# Urukul_DIOT_Connectors_P1_P6.net
KiCad netlist of a schematic drawn in Altium Designer
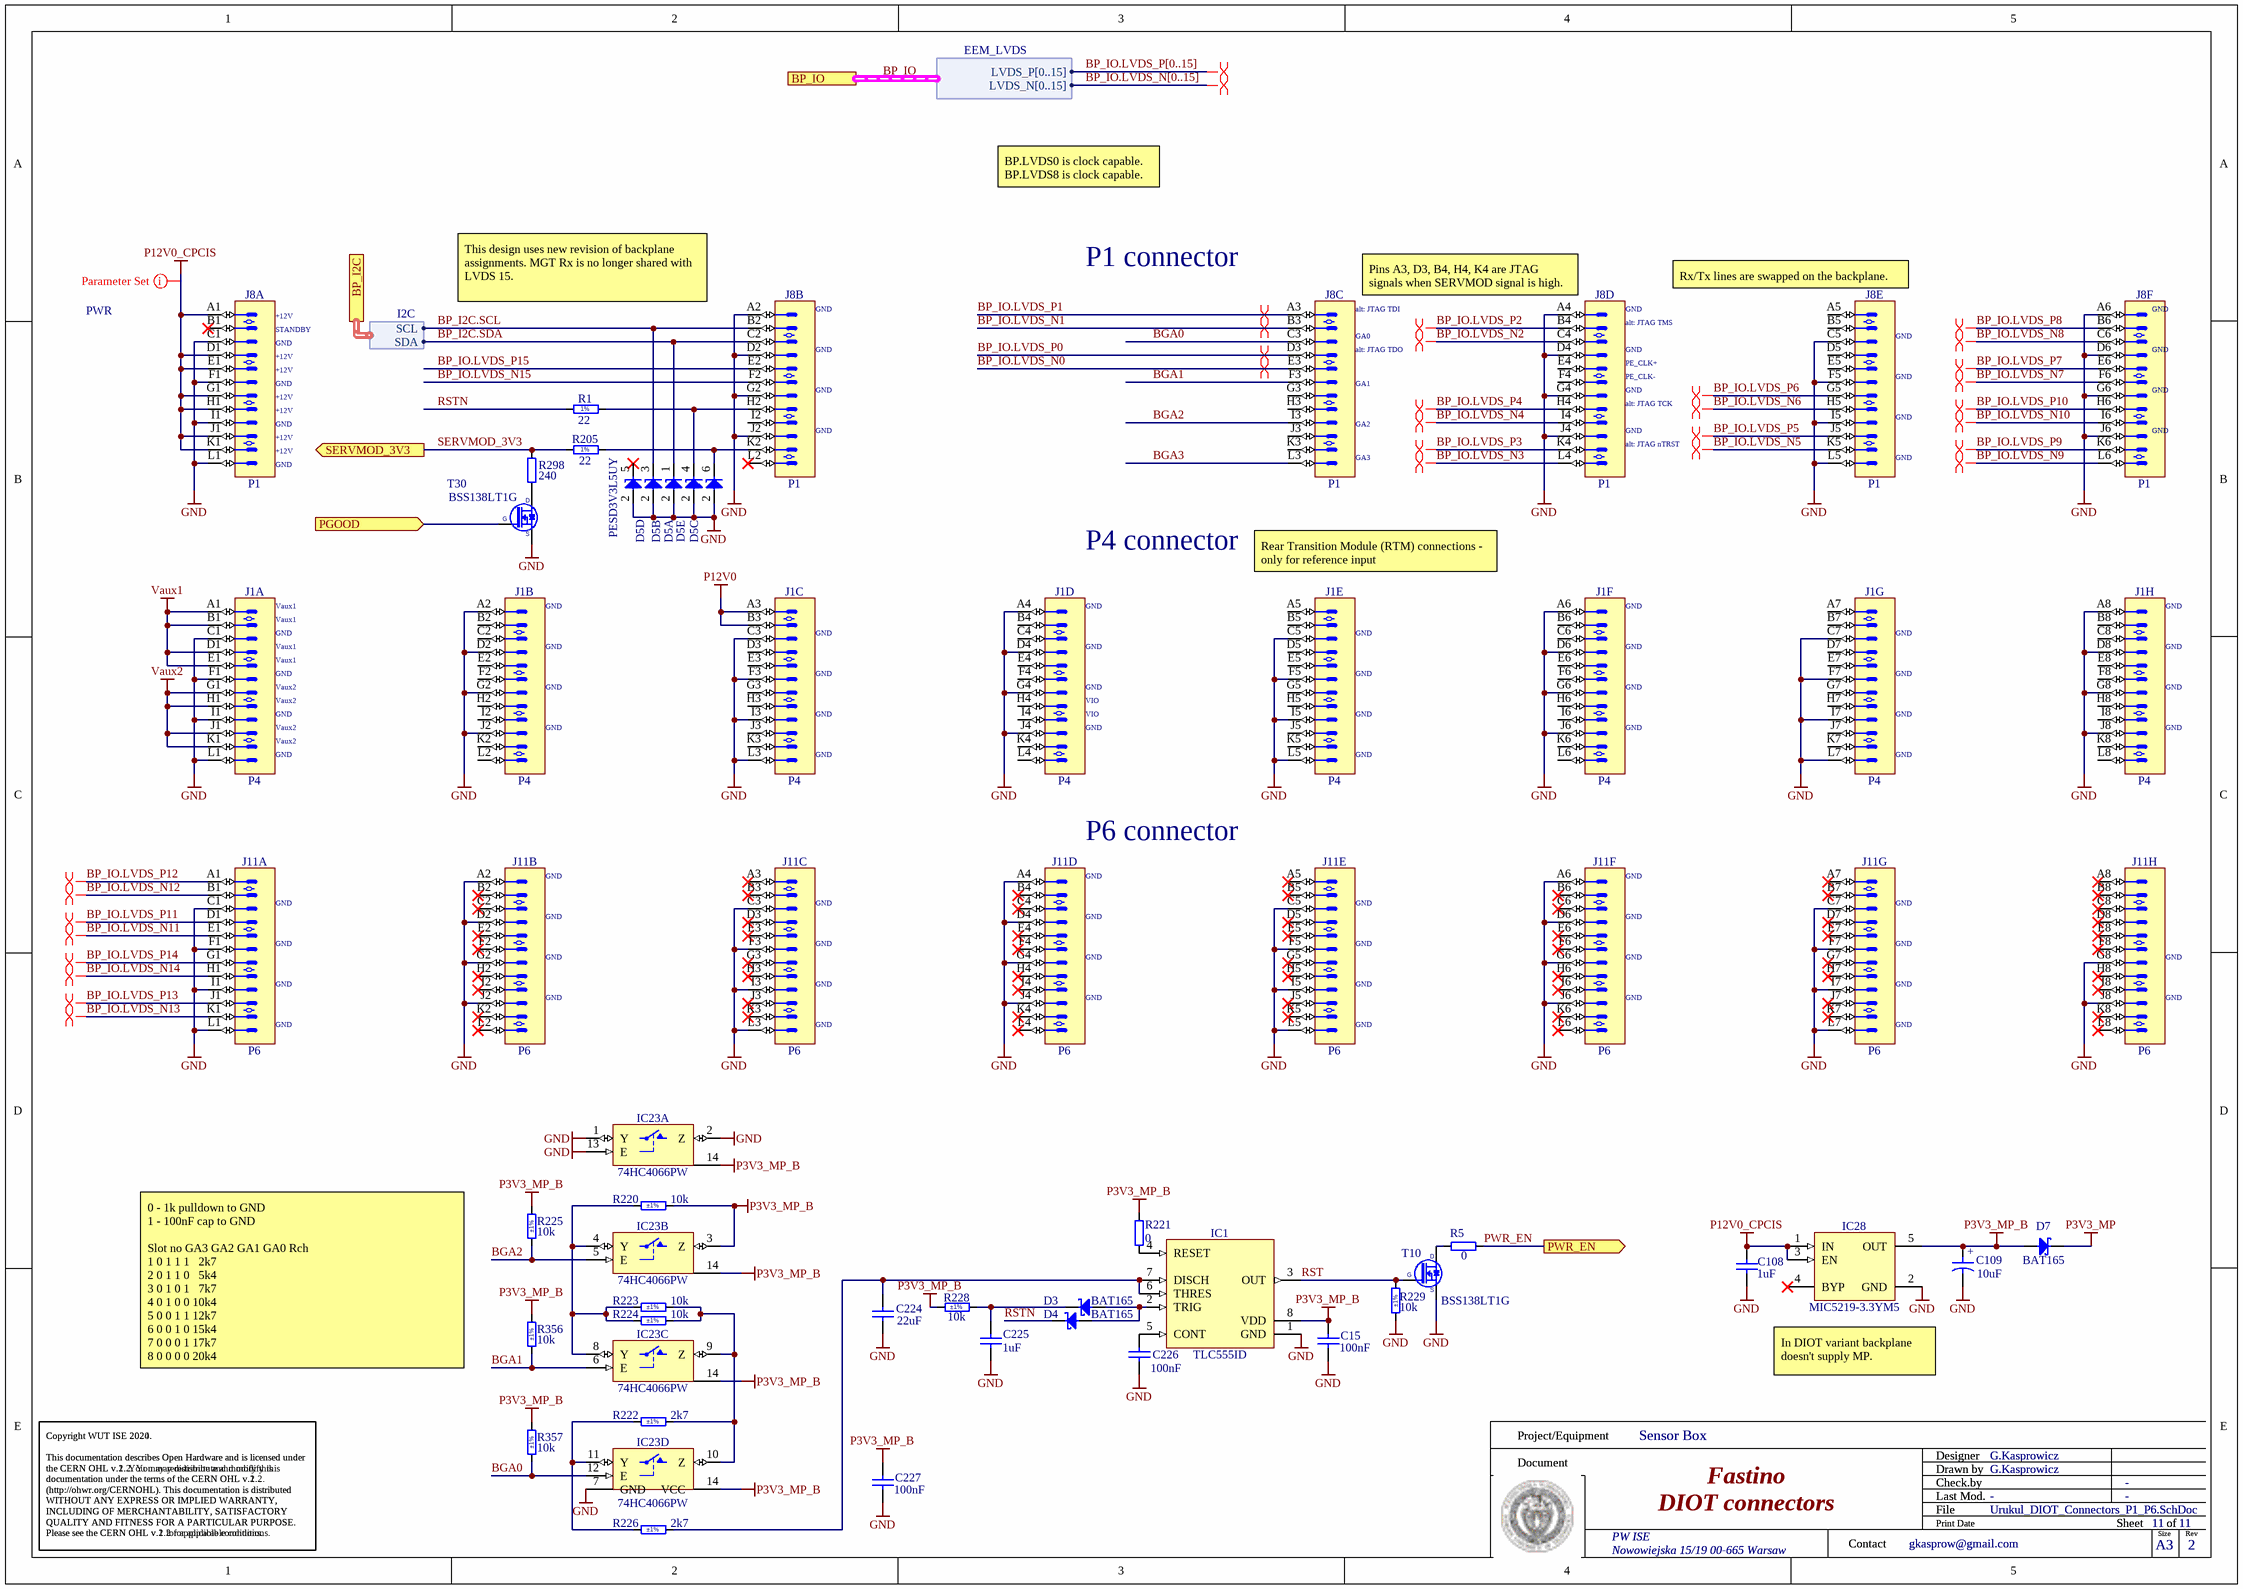
[diagram p0: Urukul_DIOT_Connectors_P1_P6.SchDoc]

(export (version "E")
  (design (tool "Eeschema 10.0.6"))
  (components
    (comp (ref "C15")
      (value "100nF")
      (footprint "CAPC1005X55N")
      (description "Non-polarised capacitor")
      (fields
        (field (name "PART NUMBER") "CC0402_100NF_16V_10%_X5R")
        (field (name "VOLTAGE") "16V")
        (field (name "AUTHOR") "CERN DEM JLC")
      )
      (libsource (lib "Capacitors") (part "Capacitor - non polarized"))
    )
    (comp (ref "C108")
      (value "1uF")
      (footprint "CAPC1608X87N")
      (description "Non-polarised capacitor")
      (fields
        (field (name "PART NUMBER") "CC0603_1UF_25V_10%_X7R")
        (field (name "VOLTAGE") "25V")
        (field (name "AUTHOR") "CERN DEM JLC")
      )
      (libsource (lib "Capacitors") (part "Capacitor - non polarized"))
    )
    (comp (ref "C109")
      (value "10uF")
      (footprint "CAPMP3216X180N")
      (description "Polarised capacitor")
      (fields
        (field (name "PART NUMBER") "CTE3216-18_10UF_16V_20%_AVX_TCJ")
        (field (name "VOLTAGE") "16V")
        (field (name "AUTHOR") "CERN DEM JLC")
      )
      (libsource (lib "Capacitors") (part "Capacitor - polarized"))
    )
    (comp (ref "C224")
      (value "22uF")
      (footprint "CAPC1608X90N")
      (description "Non-polarised capacitor")
      (fields
        (field (name "MANUFACTURER") "GENERIC")
        (field (name "PART NUMBER") "CC0603_22UF_6.3V_20%_X5R")
        (field (name "AUTHOR") "CERN DEM JLC")
      )
      (libsource (lib "Capacitors") (part "Capacitor - non polarized"))
    )
    (comp (ref "C225")
      (value "1uF")
      (footprint "CAPC1005X55N")
      (description "Non-polarised capacitor")
      (fields
        (field (name "PART NUMBER") "CC0402_1UF_16V_10%_X5R")
        (field (name "VOLTAGE") "16V")
        (field (name "AUTHOR") "CERN DEM JLC")
      )
      (libsource (lib "Capacitors") (part "Capacitor - non polarized"))
    )
    (comp (ref "C226")
      (value "100nF")
      (footprint "CAPC1005X55N")
      (description "Non-polarised capacitor")
      (fields
        (field (name "PART NUMBER") "CC0402_100NF_16V_10%_X5R")
        (field (name "VOLTAGE") "16V")
        (field (name "AUTHOR") "CERN DEM JLC")
      )
      (libsource (lib "Capacitors") (part "Capacitor - non polarized"))
    )
    (comp (ref "C227")
      (value "100nF")
      (footprint "CAPC1005X55N")
      (description "Non-polarised capacitor")
      (fields
        (field (name "PART NUMBER") "CC0402_100NF_16V_10%_X5R")
        (field (name "VOLTAGE") "16V")
        (field (name "AUTHOR") "CERN DEM JLC")
      )
      (libsource (lib "Capacitors") (part "Capacitor - non polarized"))
    )
    (comp (ref "D3")
      (value "BAT165")
      (footprint "SOD2512X110N")
      (description "Schottky Diode")
      (fields
        (field (name "MANUFACTURER") "INFINEON")
        (field (name "VOLTAGE") "40V")
        (field (name "AUTHOR") "CERN DEM JLC")
      )
      (libsource (lib "ICs And Semiconductors") (part "Diode Schottky"))
    )
    (comp (ref "D4")
      (value "BAT165")
      (footprint "SOD2512X110N")
      (description "Schottky Diode")
      (fields
        (field (name "MANUFACTURER") "INFINEON")
        (field (name "VOLTAGE") "40V")
        (field (name "AUTHOR") "CERN DEM JLC")
      )
      (libsource (lib "ICs And Semiconductors") (part "Diode Schottky"))
    )
    (comp (ref "D5")
      (value "PESD3V3L5UY")
      (footprint "SOT65P210X110-6N")
      (description "Fivefold ESD Protection Diode Arrays")
      (fields
        (field (name "VOLTAGE") "3.3V")
        (field (name "POWER") "200W")
        (field (name "AUTHOR") "CERN DEM WB")
      )
      (libsource (lib "ICs And Semiconductors") (part "PESD Array 5diodes 6pins Common anode2"))
    )
    (comp (ref "D7")
      (value "BAT165")
      (footprint "SOD2512X110N")
      (description "Schottky Diode")
      (fields
        (field (name "MANUFACTURER") "INFINEON")
        (field (name "VOLTAGE") "40V")
        (field (name "AUTHOR") "CERN DEM JLC")
      )
      (libsource (lib "ICs And Semiconductors") (part "Diode Schottky"))
    )
    (comp (ref "IC1")
      (value "TLC555ID")
      (footprint "SOIC127P600X175-8N")
      (description "LinCMOS Timer")
      (fields (field (name "MANUFACTURER") "TEXAS INSTRUMENTS") (field (name "AUTHOR") "CERN DEM JMW"))
      (libsource (lib "ICs And Semiconductors") (part "TLC555"))
    )
    (comp (ref "IC23")
      (value "74HC4066PW")
      (footprint "SOP65P640X110-14N")
      (fields (field (name "MANUFACTURER") "NXP SEMICONDUCTORS") (field (name "AUTHOR") "CERN DEM JLC"))
      (libsource (lib "ICs And Semiconductors") (part "4066"))
    )
    (comp (ref "IC28")
      (value "MIC5219-3.3YM5")
      (footprint "SOT95P280X145-5N")
      (description "500mA Peak Output LDO Regulator")
      (fields (field (name "MANUFACTURER") "MICROCHIP TECHNOLOGY") (field (name "AUTHOR") "CERN DEM WB"))
      (libsource (lib "ICs And Semiconductors") (part "MIC5219-X.XYM5"))
    )
    (comp (ref "J1")
      (value "P4")
      (footprint "AMPHENOL_10052837-101LF")
      (description "96 Contacts Header, 8 Columns, 4 Pairs per Column")
      (fields
        (field (name "PART NUMBER") "AMPHENOL_10052837-101LF")
        (field (name "MANUFACTURER") "AMPHENOL")
        (field (name "AUTHOR") "CERN DEM MR")
      )
      (libsource (lib "Connectors") (part "AMPHENOL_10052837-101LF"))
    )
    (comp (ref "J8")
      (value "P1")
      (footprint "AMPHENOL_10052825-101LF")
      (description "72 Contacts Header, 6 Columns, 4 Pairs per Column")
      (fields
        (field (name "PART NUMBER") "AMPHENOL_10052825-101LF")
        (field (name "MANUFACTURER") "AMPHENOL")
        (field (name "AUTHOR") "CERN DEM MR")
      )
      (libsource (lib "Connectors") (part "AMPHENOL_10052825-101LF"))
    )
    (comp (ref "J11")
      (value "P6")
      (footprint "AMPHENOL_10052838-101LF")
      (description "96 Contacts Header, 8 Columns, 4 Pairs per Column")
      (fields
        (field (name "PART NUMBER") "AMPHENOL_10052838-101LF")
        (field (name "MANUFACTURER") "AMPHENOL")
        (field (name "AUTHOR") "CERN DEM MR")
      )
      (libsource (lib "Connectors") (part "AMPHENOL_10052838-101LF"))
    )
    (comp (ref "R1")
      (value "22")
      (footprint "RESC1005X40N")
      (description "Resistor - 1%")
      (fields
        (field (name "PART NUMBER") "R0402_22R_1%_0.0625W_100PPM")
        (field (name "POWER") "0.0625W")
        (field (name "AUTHOR") "CERN DEM JLC")
      )
      (libsource (lib "Resistors") (part "Resistor - 1%"))
    )
    (comp (ref "R5")
      (value "0")
      (footprint "RESC1005X40N")
      (description "Resistor")
      (fields
        (field (name "PART NUMBER") "R0402_0R_JUMPER")
        (field (name "MANUFACTURER") "GENERIC")
        (field (name "AUTHOR") "CERN DEM JLC")
      )
      (libsource (lib "Resistors") (part "Resistor"))
    )
    (comp (ref "R205")
      (value "22")
      (footprint "RESC1005X40N")
      (description "Resistor - 1%")
      (fields
        (field (name "PART NUMBER") "R0402_22R_1%_0.0625W_100PPM")
        (field (name "POWER") "0.0625W")
        (field (name "AUTHOR") "CERN DEM JLC")
      )
      (libsource (lib "Resistors") (part "Resistor - 1%"))
    )
    (comp (ref "R220")
      (value "10k")
      (footprint "RESC1005X40N")
      (description "Resistor - 1%")
      (fields
        (field (name "PART NUMBER") "R0402_10K_1%_0.0625W_100PPM")
        (field (name "POWER") "0.0625W")
        (field (name "TOLERANCE") "±1%")
        (field (name "AUTHOR") "CERN DEM JLC")
      )
      (libsource (lib "Resistors") (part "Resistor - 1%"))
    )
    (comp (ref "R221")
      (value "0")
      (footprint "RESC1005X40N")
      (description "Resistor")
      (fields
        (field (name "PART NUMBER") "R0402_0R_JUMPER")
        (field (name "MANUFACTURER") "GENERIC")
        (field (name "AUTHOR") "CERN DEM JLC")
      )
      (libsource (lib "Resistors") (part "Resistor"))
    )
    (comp (ref "R222")
      (value "2k7")
      (footprint "RESC1608X55N")
      (description "Resistor - 1%")
      (fields
        (field (name "PART NUMBER") "R0603_2K7_1%_0.1W_100PPM")
        (field (name "POWER") "0.1W")
        (field (name "TOLERANCE") "±1%")
        (field (name "AUTHOR") "CERN DEM JLC")
      )
      (libsource (lib "Resistors") (part "Resistor - 1%"))
    )
    (comp (ref "R223")
      (value "10k")
      (footprint "RESC1005X40N")
      (description "Resistor - 1%")
      (fields
        (field (name "PART NUMBER") "R0402_10K_1%_0.0625W_100PPM")
        (field (name "POWER") "0.0625W")
        (field (name "TOLERANCE") "±1%")
        (field (name "AUTHOR") "CERN DEM JLC")
      )
      (libsource (lib "Resistors") (part "Resistor - 1%"))
    )
    (comp (ref "R224")
      (value "10k")
      (footprint "RESC1005X40N")
      (description "Resistor - 1%")
      (fields
        (field (name "PART NUMBER") "R0402_10K_1%_0.0625W_100PPM")
        (field (name "POWER") "0.0625W")
        (field (name "TOLERANCE") "±1%")
        (field (name "AUTHOR") "CERN DEM JLC")
      )
      (libsource (lib "Resistors") (part "Resistor - 1%"))
    )
    (comp (ref "R225")
      (value "10k")
      (footprint "RESC1005X40N")
      (description "Resistor - 1%")
      (fields
        (field (name "PART NUMBER") "R0402_10K_1%_0.0625W_100PPM")
        (field (name "POWER") "0.0625W")
        (field (name "TOLERANCE") "±1%")
        (field (name "AUTHOR") "CERN DEM JLC")
      )
      (libsource (lib "Resistors") (part "Resistor - 1%"))
    )
    (comp (ref "R226")
      (value "2k7")
      (footprint "RESC1608X55N")
      (description "Resistor - 1%")
      (fields
        (field (name "PART NUMBER") "R0603_2K7_1%_0.1W_100PPM")
        (field (name "POWER") "0.1W")
        (field (name "TOLERANCE") "±1%")
        (field (name "AUTHOR") "CERN DEM JLC")
      )
      (libsource (lib "Resistors") (part "Resistor - 1%"))
    )
    (comp (ref "R228")
      (value "10k")
      (footprint "RESC1005X40N")
      (description "Resistor - 1%")
      (fields
        (field (name "TOLERANCE") "±1%")
        (field (name "PART NUMBER") "R0402_10K_1%_0.0625W_100PPM")
        (field (name "POWER") "0.0625W")
        (field (name "AUTHOR") "CERN DEM JLC")
      )
      (libsource (lib "Resistors") (part "Resistor - 1%"))
    )
    (comp (ref "R229")
      (value "10k")
      (footprint "RESC1005X40N")
      (description "Resistor - 1%")
      (fields
        (field (name "TOLERANCE") "±1%")
        (field (name "PART NUMBER") "R0402_10K_1%_0.0625W_100PPM")
        (field (name "POWER") "0.0625W")
        (field (name "AUTHOR") "CERN DEM JLC")
      )
      (libsource (lib "Resistors") (part "Resistor - 1%"))
    )
    (comp (ref "R298")
      (value "240")
      (footprint "RESC1005X40N")
      (description "Resistor - 1%")
      (fields
        (field (name "PART NUMBER") "R0402_240R_1%_0.0625W_100PPM")
        (field (name "POWER") "0.0625W")
        (field (name "AUTHOR") "CERN DEM JLC")
      )
      (libsource (lib "Resistors") (part "Resistor - 1%"))
    )
    (comp (ref "R356")
      (value "10k")
      (footprint "RESC1005X40N")
      (description "Resistor - 1%")
      (fields
        (field (name "PART NUMBER") "R0402_10K_1%_0.0625W_100PPM")
        (field (name "POWER") "0.0625W")
        (field (name "TOLERANCE") "±1%")
        (field (name "AUTHOR") "CERN DEM JLC")
      )
      (libsource (lib "Resistors") (part "Resistor - 1%"))
    )
    (comp (ref "R357")
      (value "10k")
      (footprint "RESC1005X40N")
      (description "Resistor - 1%")
      (fields
        (field (name "PART NUMBER") "R0402_10K_1%_0.0625W_100PPM")
        (field (name "POWER") "0.0625W")
        (field (name "TOLERANCE") "±1%")
        (field (name "AUTHOR") "CERN DEM JLC")
      )
      (libsource (lib "Resistors") (part "Resistor - 1%"))
    )
    (comp (ref "T10")
      (value "BSS138LT1G")
      (footprint "SOT95P240X110-3N")
      (description "N-CHANNEL MOSFET WITH DIODE")
      (fields (field (name "MANUFACTURER") "ON SEMICONDUCTOR") (field (name "AUTHOR") "CERN DEM JLC"))
      (libsource (lib "ICs And Semiconductors") (part "N-MOSFET-D 1G 2S 3D"))
    )
    (comp (ref "T30")
      (value "BSS138LT1G")
      (footprint "SOT95P240X110-3N")
      (description "N-CHANNEL MOSFET WITH DIODE")
      (fields (field (name "MANUFACTURER") "ON SEMICONDUCTOR") (field (name "AUTHOR") "CERN DEM JLC"))
      (libsource (lib "ICs And Semiconductors") (part "N-MOSFET-D 1G 2S 3D"))
    )
  )
  (nets
    (net (code "3") (name "/BGA0") (class "Default")
      (node (ref "IC23") (pin "12") (pinfunction "E_12") (pintype "input"))
      (node (ref "J8") (pin "C3") (pinfunction "C3_C3") (pintype "bidirectional"))
      (node (ref "R357") (pin "1") (pinfunction "1_1") (pintype "passive"))
    )
    (net (code "4") (name "/BGA1") (class "Default")
      (node (ref "IC23") (pin "6") (pinfunction "E_6") (pintype "input"))
      (node (ref "J8") (pin "F3") (pinfunction "F3_F3") (pintype "bidirectional"))
      (node (ref "R356") (pin "1") (pinfunction "1_1") (pintype "passive"))
    )
    (net (code "5") (name "/BGA2") (class "Default")
      (node (ref "IC23") (pin "5") (pinfunction "E_5") (pintype "input"))
      (node (ref "J8") (pin "I3") (pinfunction "I3_I3") (pintype "bidirectional"))
      (node (ref "R225") (pin "1") (pinfunction "1_1") (pintype "passive"))
    )
    (net (code "6") (name "/BGA3") (class "Default")
      (node (ref "J8") (pin "L3") (pinfunction "L3_L3") (pintype "bidirectional"))
    )
    (net (code "7") (name "/BP_I2C.SCL") (class "Default")
      (node (ref "D5") (pin "3") (pinfunction "C_3") (pintype "passive"))
      (node (ref "J8") (pin "B2") (pinfunction "B2_B2") (pintype "bidirectional"))
    )
    (net (code "8") (name "/BP_I2C.SDA") (class "Default")
      (node (ref "D5") (pin "1") (pinfunction "C_1") (pintype "passive"))
      (node (ref "J8") (pin "C2") (pinfunction "C2_C2") (pintype "bidirectional"))
    )
    (net (code "9") (name "/BP_IO.LVDS_N0") (class "Default")
      (node (ref "J8") (pin "E3") (pinfunction "E3_E3") (pintype "bidirectional"))
    )
    (net (code "10") (name "/BP_IO.LVDS_N1") (class "Default")
      (node (ref "J8") (pin "B3") (pinfunction "B3_B3") (pintype "bidirectional"))
    )
    (net (code "11") (name "/BP_IO.LVDS_N2") (class "Default")
      (node (ref "J8") (pin "C4") (pinfunction "C4_C4") (pintype "bidirectional"))
    )
    (net (code "12") (name "/BP_IO.LVDS_N3") (class "Default")
      (node (ref "J8") (pin "L4") (pinfunction "L4_L4") (pintype "bidirectional"))
    )
    (net (code "13") (name "/BP_IO.LVDS_N4") (class "Default")
      (node (ref "J8") (pin "I4") (pinfunction "I4_I4") (pintype "bidirectional"))
    )
    (net (code "14") (name "/BP_IO.LVDS_N5") (class "Default")
      (node (ref "J8") (pin "K5") (pinfunction "K5_K5") (pintype "bidirectional"))
    )
    (net (code "15") (name "/BP_IO.LVDS_N6") (class "Default")
      (node (ref "J8") (pin "H5") (pinfunction "H5_H5") (pintype "bidirectional"))
    )
    (net (code "16") (name "/BP_IO.LVDS_N7") (class "Default")
      (node (ref "J8") (pin "F6") (pinfunction "F6_F6") (pintype "bidirectional"))
    )
    (net (code "17") (name "/BP_IO.LVDS_N8") (class "Default")
      (node (ref "J8") (pin "C6") (pinfunction "C6_C6") (pintype "bidirectional"))
    )
    (net (code "18") (name "/BP_IO.LVDS_N9") (class "Default")
      (node (ref "J8") (pin "L6") (pinfunction "L6_L6") (pintype "bidirectional"))
    )
    (net (code "19") (name "/BP_IO.LVDS_N10") (class "Default")
      (node (ref "J8") (pin "I6") (pinfunction "I6_I6") (pintype "bidirectional"))
    )
    (net (code "20") (name "/BP_IO.LVDS_N11") (class "Default")
      (node (ref "J11") (pin "E1") (pinfunction "E1_E1") (pintype "bidirectional"))
    )
    (net (code "21") (name "/BP_IO.LVDS_N12") (class "Default")
      (node (ref "J11") (pin "B1") (pinfunction "B1_B1") (pintype "bidirectional"))
    )
    (net (code "22") (name "/BP_IO.LVDS_N13") (class "Default")
      (node (ref "J11") (pin "K1") (pinfunction "K1_K1") (pintype "bidirectional"))
    )
    (net (code "23") (name "/BP_IO.LVDS_N14") (class "Default")
      (node (ref "J11") (pin "H1") (pinfunction "H1_H1") (pintype "bidirectional"))
    )
    (net (code "24") (name "/BP_IO.LVDS_N15") (class "Default")
      (node (ref "J8") (pin "F2") (pinfunction "F2_F2") (pintype "bidirectional"))
    )
    (net (code "26") (name "/BP_IO.LVDS_P0") (class "Default")
      (node (ref "J8") (pin "D3") (pinfunction "D3_D3") (pintype "bidirectional"))
    )
    (net (code "27") (name "/BP_IO.LVDS_P1") (class "Default")
      (node (ref "J8") (pin "A3") (pinfunction "A3_A3") (pintype "bidirectional"))
    )
    (net (code "28") (name "/BP_IO.LVDS_P2") (class "Default")
      (node (ref "J8") (pin "B4") (pinfunction "B4_B4") (pintype "bidirectional"))
    )
    (net (code "29") (name "/BP_IO.LVDS_P3") (class "Default")
      (node (ref "J8") (pin "K4") (pinfunction "K4_K4") (pintype "bidirectional"))
    )
    (net (code "30") (name "/BP_IO.LVDS_P4") (class "Default")
      (node (ref "J8") (pin "H4") (pinfunction "H4_H4") (pintype "bidirectional"))
    )
    (net (code "31") (name "/BP_IO.LVDS_P5") (class "Default")
      (node (ref "J8") (pin "J5") (pinfunction "J5_J5") (pintype "bidirectional"))
    )
    (net (code "32") (name "/BP_IO.LVDS_P6") (class "Default")
      (node (ref "J8") (pin "G5") (pinfunction "G5_G5") (pintype "bidirectional"))
    )
    (net (code "33") (name "/BP_IO.LVDS_P7") (class "Default")
      (node (ref "J8") (pin "E6") (pinfunction "E6_E6") (pintype "bidirectional"))
    )
    (net (code "34") (name "/BP_IO.LVDS_P8") (class "Default")
      (node (ref "J8") (pin "B6") (pinfunction "B6_B6") (pintype "bidirectional"))
    )
    (net (code "35") (name "/BP_IO.LVDS_P9") (class "Default")
      (node (ref "J8") (pin "K6") (pinfunction "K6_K6") (pintype "bidirectional"))
    )
    (net (code "36") (name "/BP_IO.LVDS_P10") (class "Default")
      (node (ref "J8") (pin "H6") (pinfunction "H6_H6") (pintype "bidirectional"))
    )
    (net (code "37") (name "/BP_IO.LVDS_P11") (class "Default")
      (node (ref "J11") (pin "D1") (pinfunction "D1_D1") (pintype "bidirectional"))
    )
    (net (code "38") (name "/BP_IO.LVDS_P12") (class "Default")
      (node (ref "J11") (pin "A1") (pinfunction "A1_A1") (pintype "bidirectional"))
    )
    (net (code "39") (name "/BP_IO.LVDS_P13") (class "Default")
      (node (ref "J11") (pin "J1") (pinfunction "J1_J1") (pintype "bidirectional"))
    )
    (net (code "40") (name "/BP_IO.LVDS_P14") (class "Default")
      (node (ref "J11") (pin "G1") (pinfunction "G1_G1") (pintype "bidirectional"))
    )
    (net (code "41") (name "/BP_IO.LVDS_P15") (class "Default")
      (node (ref "J8") (pin "E2") (pinfunction "E2_E2") (pintype "bidirectional"))
    )
    (net (code "42") (name "/PGOOD") (class "Default")
      (node (ref "T30") (pin "1") (pinfunction "G_1") (pintype "passive"))
    )
    (net (code "43") (name "/PWR_EN") (class "Default")
      (node (ref "R5") (pin "1") (pinfunction "1_1") (pintype "passive"))
    )
    (net (code "44") (name "/RST") (class "Default")
      (node (ref "IC1") (pin "3") (pinfunction "OUT_3") (pintype "output"))
      (node (ref "R229") (pin "2") (pinfunction "2_2") (pintype "passive"))
      (node (ref "T10") (pin "1") (pinfunction "G_1") (pintype "passive"))
    )
    (net (code "45") (name "/RSTN") (class "Default")
      (node (ref "D4") (pin "1") (pinfunction "C_1") (pintype "passive"))
      (node (ref "R1") (pin "1") (pinfunction "1_1") (pintype "passive"))
    )
    (net (code "46") (name "/SERVMOD_3V3") (class "Default")
      (node (ref "R205") (pin "1") (pinfunction "1_1") (pintype "passive"))
      (node (ref "R298") (pin "2") (pinfunction "2_2") (pintype "passive"))
    )
    (net (code "50") (name "GND") (class "Default")
      (node (ref "C108") (pin "1") (pinfunction "1_1") (pintype "passive"))
      (node (ref "C109") (pin "2") (pinfunction "2_2") (pintype "passive"))
      (node (ref "C15") (pin "1") (pinfunction "1_1") (pintype "passive"))
      (node (ref "C224") (pin "1") (pinfunction "1_1") (pintype "passive"))
      (node (ref "C225") (pin "1") (pinfunction "1_1") (pintype "passive"))
      (node (ref "C226") (pin "1") (pinfunction "1_1") (pintype "passive"))
      (node (ref "C227") (pin "1") (pinfunction "1_1") (pintype "passive"))
      (node (ref "D5") (pin "2") (pinfunction "A_2") (pintype "passive"))
      (node (ref "IC1") (pin "1") (pinfunction "GND_1") (pintype "power_in"))
      (node (ref "IC23") (pin "1") (pinfunction "Y_1") (pintype "bidirectional"))
      (node (ref "IC23") (pin "13") (pinfunction "E_13") (pintype "input"))
      (node (ref "IC23") (pin "2") (pinfunction "Z_2") (pintype "bidirectional"))
      (node (ref "IC23") (pin "7") (pinfunction "GND_7") (pintype "power_in"))
      (node (ref "IC28") (pin "2") (pinfunction "GND_2") (pintype "power_in"))
      (node (ref "J1") (pin "A2") (pinfunction "A2_A2") (pintype "bidirectional"))
      (node (ref "J1") (pin "A4") (pinfunction "A4_A4") (pintype "bidirectional"))
      (node (ref "J1") (pin "A6") (pinfunction "A6_A6") (pintype "bidirectional"))
      (node (ref "J1") (pin "A8") (pinfunction "A8_A8") (pintype "bidirectional"))
      (node (ref "J1") (pin "C1") (pinfunction "C1_C1") (pintype "bidirectional"))
      (node (ref "J1") (pin "C3") (pinfunction "C3_C3") (pintype "bidirectional"))
      (node (ref "J1") (pin "C5") (pinfunction "C5_C5") (pintype "bidirectional"))
      (node (ref "J1") (pin "C7") (pinfunction "C7_C7") (pintype "bidirectional"))
      (node (ref "J1") (pin "D2") (pinfunction "D2_D2") (pintype "bidirectional"))
      (node (ref "J1") (pin "D4") (pinfunction "D4_D4") (pintype "bidirectional"))
      (node (ref "J1") (pin "D6") (pinfunction "D6_D6") (pintype "bidirectional"))
      (node (ref "J1") (pin "D8") (pinfunction "D8_D8") (pintype "bidirectional"))
      (node (ref "J1") (pin "F1") (pinfunction "F1_F1") (pintype "bidirectional"))
      (node (ref "J1") (pin "F3") (pinfunction "F3_F3") (pintype "bidirectional"))
      (node (ref "J1") (pin "F5") (pinfunction "F5_F5") (pintype "bidirectional"))
      (node (ref "J1") (pin "F7") (pinfunction "F7_F7") (pintype "bidirectional"))
      (node (ref "J1") (pin "G2") (pinfunction "G2_G2") (pintype "bidirectional"))
      (node (ref "J1") (pin "G4") (pinfunction "G4_G4") (pintype "bidirectional"))
      (node (ref "J1") (pin "G6") (pinfunction "G6_G6") (pintype "bidirectional"))
      (node (ref "J1") (pin "G8") (pinfunction "G8_G8") (pintype "bidirectional"))
      (node (ref "J1") (pin "I1") (pinfunction "I1_I1") (pintype "bidirectional"))
      (node (ref "J1") (pin "I3") (pinfunction "I3_I3") (pintype "bidirectional"))
      (node (ref "J1") (pin "I5") (pinfunction "I5_I5") (pintype "bidirectional"))
      (node (ref "J1") (pin "I7") (pinfunction "I7_I7") (pintype "bidirectional"))
      (node (ref "J1") (pin "J2") (pinfunction "J2_J2") (pintype "bidirectional"))
      (node (ref "J1") (pin "J4") (pinfunction "J4_J4") (pintype "bidirectional"))
      (node (ref "J1") (pin "J6") (pinfunction "J6_J6") (pintype "bidirectional"))
      (node (ref "J1") (pin "J8") (pinfunction "J8_J8") (pintype "bidirectional"))
      (node (ref "J1") (pin "L1") (pinfunction "L1_L1") (pintype "bidirectional"))
      (node (ref "J1") (pin "L3") (pinfunction "L3_L3") (pintype "bidirectional"))
      (node (ref "J1") (pin "L5") (pinfunction "L5_L5") (pintype "bidirectional"))
      (node (ref "J1") (pin "L7") (pinfunction "L7_L7") (pintype "bidirectional"))
      (node (ref "J11") (pin "A2") (pinfunction "A2_A2") (pintype "bidirectional"))
      (node (ref "J11") (pin "A4") (pinfunction "A4_A4") (pintype "bidirectional"))
      (node (ref "J11") (pin "A6") (pinfunction "A6_A6") (pintype "bidirectional"))
      (node (ref "J11") (pin "C1") (pinfunction "C1_C1") (pintype "bidirectional"))
      (node (ref "J11") (pin "C3") (pinfunction "C3_C3") (pintype "bidirectional"))
      (node (ref "J11") (pin "C5") (pinfunction "C5_C5") (pintype "bidirectional"))
      (node (ref "J11") (pin "C7") (pinfunction "C7_C7") (pintype "bidirectional"))
      (node (ref "J11") (pin "D2") (pinfunction "D2_D2") (pintype "bidirectional"))
      (node (ref "J11") (pin "D4") (pinfunction "D4_D4") (pintype "bidirectional"))
      (node (ref "J11") (pin "D6") (pinfunction "D6_D6") (pintype "bidirectional"))
      (node (ref "J11") (pin "F1") (pinfunction "F1_F1") (pintype "bidirectional"))
      (node (ref "J11") (pin "F3") (pinfunction "F3_F3") (pintype "bidirectional"))
      (node (ref "J11") (pin "F5") (pinfunction "F5_F5") (pintype "bidirectional"))
      (node (ref "J11") (pin "F7") (pinfunction "F7_F7") (pintype "bidirectional"))
      (node (ref "J11") (pin "G2") (pinfunction "G2_G2") (pintype "bidirectional"))
      (node (ref "J11") (pin "G4") (pinfunction "G4_G4") (pintype "bidirectional"))
      (node (ref "J11") (pin "G6") (pinfunction "G6_G6") (pintype "bidirectional"))
      (node (ref "J11") (pin "G8") (pinfunction "G8_G8") (pintype "bidirectional"))
      (node (ref "J11") (pin "I1") (pinfunction "I1_I1") (pintype "bidirectional"))
      (node (ref "J11") (pin "I3") (pinfunction "I3_I3") (pintype "bidirectional"))
      (node (ref "J11") (pin "I5") (pinfunction "I5_I5") (pintype "bidirectional"))
      (node (ref "J11") (pin "I7") (pinfunction "I7_I7") (pintype "bidirectional"))
      (node (ref "J11") (pin "J2") (pinfunction "J2_J2") (pintype "bidirectional"))
      (node (ref "J11") (pin "J4") (pinfunction "J4_J4") (pintype "bidirectional"))
      (node (ref "J11") (pin "J6") (pinfunction "J6_J6") (pintype "bidirectional"))
      (node (ref "J11") (pin "J8") (pinfunction "J8_J8") (pintype "bidirectional"))
      (node (ref "J11") (pin "L1") (pinfunction "L1_L1") (pintype "bidirectional"))
      (node (ref "J11") (pin "L3") (pinfunction "L3_L3") (pintype "bidirectional"))
      (node (ref "J11") (pin "L5") (pinfunction "L5_L5") (pintype "bidirectional"))
      (node (ref "J11") (pin "L7") (pinfunction "L7_L7") (pintype "bidirectional"))
      (node (ref "J8") (pin "A2") (pinfunction "A2_A2") (pintype "bidirectional"))
      (node (ref "J8") (pin "A4") (pinfunction "A4_A4") (pintype "bidirectional"))
      (node (ref "J8") (pin "A6") (pinfunction "A6_A6") (pintype "bidirectional"))
      (node (ref "J8") (pin "C1") (pinfunction "C1_C1") (pintype "bidirectional"))
      (node (ref "J8") (pin "C5") (pinfunction "C5_C5") (pintype "bidirectional"))
      (node (ref "J8") (pin "D2") (pinfunction "D2_D2") (pintype "bidirectional"))
      (node (ref "J8") (pin "D4") (pinfunction "D4_D4") (pintype "bidirectional"))
      (node (ref "J8") (pin "D6") (pinfunction "D6_D6") (pintype "bidirectional"))
      (node (ref "J8") (pin "F1") (pinfunction "F1_F1") (pintype "bidirectional"))
      (node (ref "J8") (pin "F5") (pinfunction "F5_F5") (pintype "bidirectional"))
      (node (ref "J8") (pin "G2") (pinfunction "G2_G2") (pintype "bidirectional"))
      (node (ref "J8") (pin "G4") (pinfunction "G4_G4") (pintype "bidirectional"))
      (node (ref "J8") (pin "G6") (pinfunction "G6_G6") (pintype "bidirectional"))
      (node (ref "J8") (pin "I1") (pinfunction "I1_I1") (pintype "bidirectional"))
      (node (ref "J8") (pin "I5") (pinfunction "I5_I5") (pintype "bidirectional"))
      (node (ref "J8") (pin "J2") (pinfunction "J2_J2") (pintype "bidirectional"))
      (node (ref "J8") (pin "J4") (pinfunction "J4_J4") (pintype "bidirectional"))
      (node (ref "J8") (pin "J6") (pinfunction "J6_J6") (pintype "bidirectional"))
      (node (ref "J8") (pin "L1") (pinfunction "L1_L1") (pintype "bidirectional"))
      (node (ref "J8") (pin "L5") (pinfunction "L5_L5") (pintype "bidirectional"))
      (node (ref "R229") (pin "1") (pinfunction "1_1") (pintype "passive"))
      (node (ref "T10") (pin "2") (pinfunction "S_2") (pintype "passive"))
      (node (ref "T30") (pin "2") (pinfunction "S_2") (pintype "passive"))
    )
    (net (code "51") (name "Net-(D3-A)") (class "Default")
      (node (ref "D3") (pin "2") (pinfunction "A_2") (pintype "passive"))
      (node (ref "D4") (pin "2") (pinfunction "A_2") (pintype "passive"))
      (node (ref "IC1") (pin "2") (pinfunction "TRIG_2") (pintype "input"))
    )
    (net (code "52") (name "Net-(D3-C)") (class "Default")
      (node (ref "C225") (pin "2") (pinfunction "2_2") (pintype "passive"))
      (node (ref "D3") (pin "1") (pinfunction "C_1") (pintype "passive"))
      (node (ref "R228") (pin "2") (pinfunction "2_2") (pintype "passive"))
    )
    (net (code "53") (name "Net-(D5C-C)") (class "Default")
      (node (ref "D5") (pin "4") (pinfunction "C_4") (pintype "passive"))
      (node (ref "J8") (pin "H2") (pinfunction "H2_H2") (pintype "bidirectional"))
      (node (ref "R1") (pin "2") (pinfunction "2_2") (pintype "passive"))
    )
    (net (code "54") (name "Net-(D5E-C)") (class "Default")
      (node (ref "D5") (pin "6") (pinfunction "C_6") (pintype "passive"))
      (node (ref "J8") (pin "K2") (pinfunction "K2_K2") (pintype "bidirectional"))
      (node (ref "R205") (pin "2") (pinfunction "2_2") (pintype "passive"))
    )
    (net (code "55") (name "Net-(IC1-CONT)") (class "Default")
      (node (ref "C226") (pin "2") (pinfunction "2_2") (pintype "passive"))
      (node (ref "IC1") (pin "5") (pinfunction "CONT_5") (pintype "input"))
    )
    (net (code "56") (name "Net-(IC1-DISCH)") (class "Default")
      (node (ref "C224") (pin "2") (pinfunction "2_2") (pintype "passive"))
      (node (ref "IC1") (pin "6") (pinfunction "THRES_6") (pintype "input"))
      (node (ref "IC1") (pin "7") (pinfunction "DISCH_7") (pintype "input"))
      (node (ref "R226") (pin "2") (pinfunction "2_2") (pintype "passive"))
    )
    (net (code "57") (name "Net-(IC1-RESET)") (class "Default")
      (node (ref "IC1") (pin "4") (pinfunction "RESET_4") (pintype "input"))
      (node (ref "R221") (pin "1") (pinfunction "1_1") (pintype "passive"))
    )
    (net (code "58") (name "Net-(IC23B-Y)") (class "Default")
      (node (ref "IC23") (pin "4") (pinfunction "Y_4") (pintype "bidirectional"))
      (node (ref "IC23") (pin "8") (pinfunction "Y_8") (pintype "bidirectional"))
      (node (ref "R220") (pin "1") (pinfunction "1_1") (pintype "passive"))
      (node (ref "R223") (pin "1") (pinfunction "1_1") (pintype "passive"))
      (node (ref "R224") (pin "1") (pinfunction "1_1") (pintype "passive"))
    )
    (net (code "59") (name "Net-(IC23C-Z)") (class "Default")
      (node (ref "IC23") (pin "10") (pinfunction "Z_10") (pintype "bidirectional"))
      (node (ref "IC23") (pin "9") (pinfunction "Z_9") (pintype "bidirectional"))
      (node (ref "R222") (pin "2") (pinfunction "2_2") (pintype "passive"))
      (node (ref "R223") (pin "2") (pinfunction "2_2") (pintype "passive"))
      (node (ref "R224") (pin "2") (pinfunction "2_2") (pintype "passive"))
    )
    (net (code "60") (name "Net-(IC23D-Y)") (class "Default")
      (node (ref "IC23") (pin "11") (pinfunction "Y_11") (pintype "bidirectional"))
      (node (ref "R222") (pin "1") (pinfunction "1_1") (pintype "passive"))
      (node (ref "R226") (pin "1") (pinfunction "1_1") (pintype "passive"))
    )
    (net (code "61") (name "Net-(T10-D)") (class "Default")
      (node (ref "R5") (pin "2") (pinfunction "2_2") (pintype "passive"))
      (node (ref "T10") (pin "3") (pinfunction "D_3") (pintype "passive"))
    )
    (net (code "62") (name "Net-(T30-D)") (class "Default")
      (node (ref "R298") (pin "1") (pinfunction "1_1") (pintype "passive"))
      (node (ref "T30") (pin "3") (pinfunction "D_3") (pintype "passive"))
    )
    (net (code "63") (name "P3V3_MP") (class "Default")
      (node (ref "D7") (pin "1") (pinfunction "C_1") (pintype "passive"))
    )
    (net (code "64") (name "P3V3_MP_B") (class "Default")
      (node (ref "C109") (pin "1") (pinfunction "1_1") (pintype "passive"))
      (node (ref "C15") (pin "2") (pinfunction "2_2") (pintype "passive"))
      (node (ref "C227") (pin "2") (pinfunction "2_2") (pintype "passive"))
      (node (ref "D7") (pin "2") (pinfunction "A_2") (pintype "passive"))
      (node (ref "IC1") (pin "8") (pinfunction "VDD_8") (pintype "power_in"))
      (node (ref "IC23") (pin "14") (pinfunction "VCC_14") (pintype "power_in"))
      (node (ref "IC23") (pin "3") (pinfunction "Z_3") (pintype "bidirectional"))
      (node (ref "IC28") (pin "5") (pinfunction "OUT_5") (pintype "power_in"))
      (node (ref "R220") (pin "2") (pinfunction "2_2") (pintype "passive"))
      (node (ref "R221") (pin "2") (pinfunction "2_2") (pintype "passive"))
      (node (ref "R225") (pin "2") (pinfunction "2_2") (pintype "passive"))
      (node (ref "R228") (pin "1") (pinfunction "1_1") (pintype "passive"))
      (node (ref "R356") (pin "2") (pinfunction "2_2") (pintype "passive"))
      (node (ref "R357") (pin "2") (pinfunction "2_2") (pintype "passive"))
    )
    (net (code "65") (name "P12V0") (class "Default")
      (node (ref "J1") (pin "A3") (pinfunction "A3_A3") (pintype "bidirectional"))
      (node (ref "J1") (pin "B3") (pinfunction "B3_B3") (pintype "bidirectional"))
    )
    (net (code "66") (name "P12V0_CPCIS") (class "Default")
      (node (ref "C108") (pin "2") (pinfunction "2_2") (pintype "passive"))
      (node (ref "IC28") (pin "1") (pinfunction "IN_1") (pintype "input"))
      (node (ref "IC28") (pin "3") (pinfunction "EN_3") (pintype "input"))
      (node (ref "J8") (pin "A1") (pinfunction "A1_A1") (pintype "bidirectional"))
      (node (ref "J8") (pin "D1") (pinfunction "D1_D1") (pintype "bidirectional"))
      (node (ref "J8") (pin "E1") (pinfunction "E1_E1") (pintype "bidirectional"))
      (node (ref "J8") (pin "G1") (pinfunction "G1_G1") (pintype "bidirectional"))
      (node (ref "J8") (pin "H1") (pinfunction "H1_H1") (pintype "bidirectional"))
      (node (ref "J8") (pin "J1") (pinfunction "J1_J1") (pintype "bidirectional"))
      (node (ref "J8") (pin "K1") (pinfunction "K1_K1") (pintype "bidirectional"))
    )
    (net (code "67") (name "Vaux1") (class "Default")
      (node (ref "J1") (pin "A1") (pinfunction "A1_A1") (pintype "bidirectional"))
      (node (ref "J1") (pin "B1") (pinfunction "B1_B1") (pintype "bidirectional"))
      (node (ref "J1") (pin "D1") (pinfunction "D1_D1") (pintype "bidirectional"))
      (node (ref "J1") (pin "E1") (pinfunction "E1_E1") (pintype "bidirectional"))
    )
    (net (code "68") (name "Vaux2") (class "Default")
      (node (ref "J1") (pin "G1") (pinfunction "G1_G1") (pintype "bidirectional"))
      (node (ref "J1") (pin "H1") (pinfunction "H1_H1") (pintype "bidirectional"))
      (node (ref "J1") (pin "J1") (pinfunction "J1_J1") (pintype "bidirectional"))
      (node (ref "J1") (pin "K1") (pinfunction "K1_K1") (pintype "bidirectional"))
    )
    (net (code "69") (name "unconnected-(D5D-C-Pad5)") (class "Default")
      (node (ref "D5") (pin "5") (pinfunction "C_5") (pintype "passive+no_connect"))
    )
    (net (code "70") (name "unconnected-(IC28-BYP-Pad4)") (class "Default")
      (node (ref "IC28") (pin "4") (pinfunction "BYP_4") (pintype "passive+no_connect"))
    )
    (net (code "71") (name "unconnected-(J1-PadA5)") (class "Default")
      (node (ref "J1") (pin "A5") (pinfunction "A5_A5") (pintype "bidirectional"))
    )
    (net (code "72") (name "unconnected-(J1-PadA7)") (class "Default")
      (node (ref "J1") (pin "A7") (pinfunction "A7_A7") (pintype "bidirectional"))
    )
    (net (code "73") (name "unconnected-(J1-PadB2)") (class "Default")
      (node (ref "J1") (pin "B2") (pinfunction "B2_B2") (pintype "bidirectional"))
    )
    (net (code "74") (name "unconnected-(J1-PadB4)") (class "Default")
      (node (ref "J1") (pin "B4") (pinfunction "B4_B4") (pintype "bidirectional"))
    )
    (net (code "75") (name "unconnected-(J1-PadB5)") (class "Default")
      (node (ref "J1") (pin "B5") (pinfunction "B5_B5") (pintype "bidirectional"))
    )
    (net (code "76") (name "unconnected-(J1-PadB6)") (class "Default")
      (node (ref "J1") (pin "B6") (pinfunction "B6_B6") (pintype "bidirectional"))
    )
    (net (code "77") (name "unconnected-(J1-PadB7)") (class "Default")
      (node (ref "J1") (pin "B7") (pinfunction "B7_B7") (pintype "bidirectional"))
    )
    (net (code "78") (name "unconnected-(J1-PadB8)") (class "Default")
      (node (ref "J1") (pin "B8") (pinfunction "B8_B8") (pintype "bidirectional"))
    )
    (net (code "79") (name "unconnected-(J1-PadC2)") (class "Default")
      (node (ref "J1") (pin "C2") (pinfunction "C2_C2") (pintype "bidirectional"))
    )
    (net (code "80") (name "unconnected-(J1-PadC4)") (class "Default")
      (node (ref "J1") (pin "C4") (pinfunction "C4_C4") (pintype "bidirectional"))
    )
    (net (code "81") (name "unconnected-(J1-PadC6)") (class "Default")
      (node (ref "J1") (pin "C6") (pinfunction "C6_C6") (pintype "bidirectional"))
    )
    (net (code "82") (name "unconnected-(J1-PadC8)") (class "Default")
      (node (ref "J1") (pin "C8") (pinfunction "C8_C8") (pintype "bidirectional"))
    )
    (net (code "83") (name "unconnected-(J1-PadD3)") (class "Default")
      (node (ref "J1") (pin "D3") (pinfunction "D3_D3") (pintype "bidirectional"))
    )
    (net (code "84") (name "unconnected-(J1-PadD5)") (class "Default")
      (node (ref "J1") (pin "D5") (pinfunction "D5_D5") (pintype "bidirectional"))
    )
    (net (code "85") (name "unconnected-(J1-PadD7)") (class "Default")
      (node (ref "J1") (pin "D7") (pinfunction "D7_D7") (pintype "bidirectional"))
    )
    (net (code "86") (name "unconnected-(J1-PadE2)") (class "Default")
      (node (ref "J1") (pin "E2") (pinfunction "E2_E2") (pintype "bidirectional"))
    )
    (net (code "87") (name "unconnected-(J1-PadE3)") (class "Default")
      (node (ref "J1") (pin "E3") (pinfunction "E3_E3") (pintype "bidirectional"))
    )
    (net (code "88") (name "unconnected-(J1-PadE4)") (class "Default")
      (node (ref "J1") (pin "E4") (pinfunction "E4_E4") (pintype "bidirectional"))
    )
    (net (code "89") (name "unconnected-(J1-PadE5)") (class "Default")
      (node (ref "J1") (pin "E5") (pinfunction "E5_E5") (pintype "bidirectional"))
    )
    (net (code "90") (name "unconnected-(J1-PadE6)") (class "Default")
      (node (ref "J1") (pin "E6") (pinfunction "E6_E6") (pintype "bidirectional"))
    )
    (net (code "91") (name "unconnected-(J1-PadE7)") (class "Default")
      (node (ref "J1") (pin "E7") (pinfunction "E7_E7") (pintype "bidirectional"))
    )
    (net (code "92") (name "unconnected-(J1-PadE8)") (class "Default")
      (node (ref "J1") (pin "E8") (pinfunction "E8_E8") (pintype "bidirectional"))
    )
    (net (code "93") (name "unconnected-(J1-PadF2)") (class "Default")
      (node (ref "J1") (pin "F2") (pinfunction "F2_F2") (pintype "bidirectional"))
    )
    (net (code "94") (name "unconnected-(J1-PadF4)") (class "Default")
      (node (ref "J1") (pin "F4") (pinfunction "F4_F4") (pintype "bidirectional"))
    )
    (net (code "95") (name "unconnected-(J1-PadF6)") (class "Default")
      (node (ref "J1") (pin "F6") (pinfunction "F6_F6") (pintype "bidirectional"))
    )
    (net (code "96") (name "unconnected-(J1-PadF8)") (class "Default")
      (node (ref "J1") (pin "F8") (pinfunction "F8_F8") (pintype "bidirectional"))
    )
    (net (code "97") (name "unconnected-(J1-PadG3)") (class "Default")
      (node (ref "J1") (pin "G3") (pinfunction "G3_G3") (pintype "bidirectional"))
    )
    (net (code "98") (name "unconnected-(J1-PadG5)") (class "Default")
      (node (ref "J1") (pin "G5") (pinfunction "G5_G5") (pintype "bidirectional"))
    )
    (net (code "99") (name "unconnected-(J1-PadG7)") (class "Default")
      (node (ref "J1") (pin "G7") (pinfunction "G7_G7") (pintype "bidirectional"))
    )
    (net (code "100") (name "unconnected-(J1-PadH2)") (class "Default")
      (node (ref "J1") (pin "H2") (pinfunction "H2_H2") (pintype "bidirectional"))
    )
    (net (code "101") (name "unconnected-(J1-PadH3)") (class "Default")
      (node (ref "J1") (pin "H3") (pinfunction "H3_H3") (pintype "bidirectional"))
    )
    (net (code "102") (name "unconnected-(J1-PadH4)") (class "Default")
      (node (ref "J1") (pin "H4") (pinfunction "H4_H4") (pintype "bidirectional"))
    )
    (net (code "103") (name "unconnected-(J1-PadH5)") (class "Default")
      (node (ref "J1") (pin "H5") (pinfunction "H5_H5") (pintype "bidirectional"))
    )
    (net (code "104") (name "unconnected-(J1-PadH6)") (class "Default")
      (node (ref "J1") (pin "H6") (pinfunction "H6_H6") (pintype "bidirectional"))
    )
    (net (code "105") (name "unconnected-(J1-PadH7)") (class "Default")
      (node (ref "J1") (pin "H7") (pinfunction "H7_H7") (pintype "bidirectional"))
    )
    (net (code "106") (name "unconnected-(J1-PadH8)") (class "Default")
      (node (ref "J1") (pin "H8") (pinfunction "H8_H8") (pintype "bidirectional"))
    )
    (net (code "107") (name "unconnected-(J1-PadI2)") (class "Default")
      (node (ref "J1") (pin "I2") (pinfunction "I2_I2") (pintype "bidirectional"))
    )
    (net (code "108") (name "unconnected-(J1-PadI4)") (class "Default")
      (node (ref "J1") (pin "I4") (pinfunction "I4_I4") (pintype "bidirectional"))
    )
    (net (code "109") (name "unconnected-(J1-PadI6)") (class "Default")
      (node (ref "J1") (pin "I6") (pinfunction "I6_I6") (pintype "bidirectional"))
    )
    (net (code "110") (name "unconnected-(J1-PadI8)") (class "Default")
      (node (ref "J1") (pin "I8") (pinfunction "I8_I8") (pintype "bidirectional"))
    )
    (net (code "111") (name "unconnected-(J1-PadJ3)") (class "Default")
      (node (ref "J1") (pin "J3") (pinfunction "J3_J3") (pintype "bidirectional"))
    )
    (net (code "112") (name "unconnected-(J1-PadJ5)") (class "Default")
      (node (ref "J1") (pin "J5") (pinfunction "J5_J5") (pintype "bidirectional"))
    )
    (net (code "113") (name "unconnected-(J1-PadJ7)") (class "Default")
      (node (ref "J1") (pin "J7") (pinfunction "J7_J7") (pintype "bidirectional"))
    )
    (net (code "114") (name "unconnected-(J1-PadK2)") (class "Default")
      (node (ref "J1") (pin "K2") (pinfunction "K2_K2") (pintype "bidirectional"))
    )
    (net (code "115") (name "unconnected-(J1-PadK3)") (class "Default")
      (node (ref "J1") (pin "K3") (pinfunction "K3_K3") (pintype "bidirectional"))
    )
    (net (code "116") (name "unconnected-(J1-PadK4)") (class "Default")
      (node (ref "J1") (pin "K4") (pinfunction "K4_K4") (pintype "bidirectional"))
    )
    (net (code "117") (name "unconnected-(J1-PadK5)") (class "Default")
      (node (ref "J1") (pin "K5") (pinfunction "K5_K5") (pintype "bidirectional"))
    )
    (net (code "118") (name "unconnected-(J1-PadK6)") (class "Default")
      (node (ref "J1") (pin "K6") (pinfunction "K6_K6") (pintype "bidirectional"))
    )
    (net (code "119") (name "unconnected-(J1-PadK7)") (class "Default")
      (node (ref "J1") (pin "K7") (pinfunction "K7_K7") (pintype "bidirectional"))
    )
    (net (code "120") (name "unconnected-(J1-PadK8)") (class "Default")
      (node (ref "J1") (pin "K8") (pinfunction "K8_K8") (pintype "bidirectional"))
    )
    (net (code "121") (name "unconnected-(J1-PadL2)") (class "Default")
      (node (ref "J1") (pin "L2") (pinfunction "L2_L2") (pintype "bidirectional"))
    )
    (net (code "122") (name "unconnected-(J1-PadL4)") (class "Default")
      (node (ref "J1") (pin "L4") (pinfunction "L4_L4") (pintype "bidirectional"))
    )
    (net (code "123") (name "unconnected-(J1-PadL6)") (class "Default")
      (node (ref "J1") (pin "L6") (pinfunction "L6_L6") (pintype "bidirectional"))
    )
    (net (code "124") (name "unconnected-(J1-PadL8)") (class "Default")
      (node (ref "J1") (pin "L8") (pinfunction "L8_L8") (pintype "bidirectional"))
    )
    (net (code "125") (name "unconnected-(J8-PadA5)") (class "Default")
      (node (ref "J8") (pin "A5") (pinfunction "A5_A5") (pintype "bidirectional"))
    )
    (net (code "126") (name "unconnected-(J8-PadB1)") (class "Default")
      (node (ref "J8") (pin "B1") (pinfunction "B1_B1") (pintype "bidirectional+no_connect"))
    )
    (net (code "127") (name "unconnected-(J8-PadB5)") (class "Default")
      (node (ref "J8") (pin "B5") (pinfunction "B5_B5") (pintype "bidirectional"))
    )
    (net (code "128") (name "unconnected-(J8-PadD5)") (class "Default")
      (node (ref "J8") (pin "D5") (pinfunction "D5_D5") (pintype "bidirectional"))
    )
    (net (code "129") (name "unconnected-(J8-PadE4)") (class "Default")
      (node (ref "J8") (pin "E4") (pinfunction "E4_E4") (pintype "bidirectional"))
    )
    (net (code "130") (name "unconnected-(J8-PadE5)") (class "Default")
      (node (ref "J8") (pin "E5") (pinfunction "E5_E5") (pintype "bidirectional"))
    )
    (net (code "131") (name "unconnected-(J8-PadF4)") (class "Default")
      (node (ref "J8") (pin "F4") (pinfunction "F4_F4") (pintype "bidirectional"))
    )
    (net (code "132") (name "unconnected-(J8-PadG3)") (class "Default")
      (node (ref "J8") (pin "G3") (pinfunction "G3_G3") (pintype "bidirectional"))
    )
    (net (code "133") (name "unconnected-(J8-PadH3)") (class "Default")
      (node (ref "J8") (pin "H3") (pinfunction "H3_H3") (pintype "bidirectional"))
    )
    (net (code "134") (name "unconnected-(J8-PadI2)") (class "Default")
      (node (ref "J8") (pin "I2") (pinfunction "I2_I2") (pintype "bidirectional"))
    )
    (net (code "135") (name "unconnected-(J8-PadJ3)") (class "Default")
      (node (ref "J8") (pin "J3") (pinfunction "J3_J3") (pintype "bidirectional"))
    )
    (net (code "136") (name "unconnected-(J8-PadK3)") (class "Default")
      (node (ref "J8") (pin "K3") (pinfunction "K3_K3") (pintype "bidirectional"))
    )
    (net (code "137") (name "unconnected-(J8-PadL2)") (class "Default")
      (node (ref "J8") (pin "L2") (pinfunction "L2_L2") (pintype "bidirectional+no_connect"))
    )
    (net (code "138") (name "unconnected-(J11-PadA3)") (class "Default")
      (node (ref "J11") (pin "A3") (pinfunction "A3_A3") (pintype "bidirectional+no_connect"))
    )
    (net (code "139") (name "unconnected-(J11-PadA5)") (class "Default")
      (node (ref "J11") (pin "A5") (pinfunction "A5_A5") (pintype "bidirectional+no_connect"))
    )
    (net (code "140") (name "unconnected-(J11-PadA7)") (class "Default")
      (node (ref "J11") (pin "A7") (pinfunction "A7_A7") (pintype "bidirectional+no_connect"))
    )
    (net (code "141") (name "unconnected-(J11-PadA8)") (class "Default")
      (node (ref "J11") (pin "A8") (pinfunction "A8_A8") (pintype "bidirectional+no_connect"))
    )
    (net (code "142") (name "unconnected-(J11-PadB2)") (class "Default")
      (node (ref "J11") (pin "B2") (pinfunction "B2_B2") (pintype "bidirectional+no_connect"))
    )
    (net (code "143") (name "unconnected-(J11-PadB3)") (class "Default")
      (node (ref "J11") (pin "B3") (pinfunction "B3_B3") (pintype "bidirectional+no_connect"))
    )
    (net (code "144") (name "unconnected-(J11-PadB4)") (class "Default")
      (node (ref "J11") (pin "B4") (pinfunction "B4_B4") (pintype "bidirectional+no_connect"))
    )
    (net (code "145") (name "unconnected-(J11-PadB5)") (class "Default")
      (node (ref "J11") (pin "B5") (pinfunction "B5_B5") (pintype "bidirectional+no_connect"))
    )
    (net (code "146") (name "unconnected-(J11-PadB6)") (class "Default")
      (node (ref "J11") (pin "B6") (pinfunction "B6_B6") (pintype "bidirectional+no_connect"))
    )
    (net (code "147") (name "unconnected-(J11-PadB7)") (class "Default")
      (node (ref "J11") (pin "B7") (pinfunction "B7_B7") (pintype "bidirectional+no_connect"))
    )
    (net (code "148") (name "unconnected-(J11-PadB8)") (class "Default")
      (node (ref "J11") (pin "B8") (pinfunction "B8_B8") (pintype "bidirectional+no_connect"))
    )
    (net (code "149") (name "unconnected-(J11-PadC2)") (class "Default")
      (node (ref "J11") (pin "C2") (pinfunction "C2_C2") (pintype "bidirectional+no_connect"))
    )
    (net (code "150") (name "unconnected-(J11-PadC4)") (class "Default")
      (node (ref "J11") (pin "C4") (pinfunction "C4_C4") (pintype "bidirectional+no_connect"))
    )
    (net (code "151") (name "unconnected-(J11-PadC6)") (class "Default")
      (node (ref "J11") (pin "C6") (pinfunction "C6_C6") (pintype "bidirectional+no_connect"))
    )
    (net (code "152") (name "unconnected-(J11-PadC8)") (class "Default")
      (node (ref "J11") (pin "C8") (pinfunction "C8_C8") (pintype "bidirectional+no_connect"))
    )
    (net (code "153") (name "unconnected-(J11-PadD3)") (class "Default")
      (node (ref "J11") (pin "D3") (pinfunction "D3_D3") (pintype "bidirectional+no_connect"))
    )
    (net (code "154") (name "unconnected-(J11-PadD5)") (class "Default")
      (node (ref "J11") (pin "D5") (pinfunction "D5_D5") (pintype "bidirectional+no_connect"))
    )
    (net (code "155") (name "unconnected-(J11-PadD7)") (class "Default")
      (node (ref "J11") (pin "D7") (pinfunction "D7_D7") (pintype "bidirectional+no_connect"))
    )
    (net (code "156") (name "unconnected-(J11-PadD8)") (class "Default")
      (node (ref "J11") (pin "D8") (pinfunction "D8_D8") (pintype "bidirectional+no_connect"))
    )
    (net (code "157") (name "unconnected-(J11-PadE2)") (class "Default")
      (node (ref "J11") (pin "E2") (pinfunction "E2_E2") (pintype "bidirectional+no_connect"))
    )
    (net (code "158") (name "unconnected-(J11-PadE3)") (class "Default")
      (node (ref "J11") (pin "E3") (pinfunction "E3_E3") (pintype "bidirectional+no_connect"))
    )
    (net (code "159") (name "unconnected-(J11-PadE4)") (class "Default")
      (node (ref "J11") (pin "E4") (pinfunction "E4_E4") (pintype "bidirectional+no_connect"))
    )
    (net (code "160") (name "unconnected-(J11-PadE5)") (class "Default")
      (node (ref "J11") (pin "E5") (pinfunction "E5_E5") (pintype "bidirectional+no_connect"))
    )
    (net (code "161") (name "unconnected-(J11-PadE6)") (class "Default")
      (node (ref "J11") (pin "E6") (pinfunction "E6_E6") (pintype "bidirectional+no_connect"))
    )
    (net (code "162") (name "unconnected-(J11-PadE7)") (class "Default")
      (node (ref "J11") (pin "E7") (pinfunction "E7_E7") (pintype "bidirectional+no_connect"))
    )
    (net (code "163") (name "unconnected-(J11-PadE8)") (class "Default")
      (node (ref "J11") (pin "E8") (pinfunction "E8_E8") (pintype "bidirectional+no_connect"))
    )
    (net (code "164") (name "unconnected-(J11-PadF2)") (class "Default")
      (node (ref "J11") (pin "F2") (pinfunction "F2_F2") (pintype "bidirectional+no_connect"))
    )
    (net (code "165") (name "unconnected-(J11-PadF4)") (class "Default")
      (node (ref "J11") (pin "F4") (pinfunction "F4_F4") (pintype "bidirectional+no_connect"))
    )
    (net (code "166") (name "unconnected-(J11-PadF6)") (class "Default")
      (node (ref "J11") (pin "F6") (pinfunction "F6_F6") (pintype "bidirectional+no_connect"))
    )
    (net (code "167") (name "unconnected-(J11-PadF8)") (class "Default")
      (node (ref "J11") (pin "F8") (pinfunction "F8_F8") (pintype "bidirectional+no_connect"))
    )
    (net (code "168") (name "unconnected-(J11-PadG3)") (class "Default")
      (node (ref "J11") (pin "G3") (pinfunction "G3_G3") (pintype "bidirectional+no_connect"))
    )
    (net (code "169") (name "unconnected-(J11-PadG5)") (class "Default")
      (node (ref "J11") (pin "G5") (pinfunction "G5_G5") (pintype "bidirectional+no_connect"))
    )
    (net (code "170") (name "unconnected-(J11-PadG7)") (class "Default")
      (node (ref "J11") (pin "G7") (pinfunction "G7_G7") (pintype "bidirectional+no_connect"))
    )
    (net (code "171") (name "unconnected-(J11-PadH2)") (class "Default")
      (node (ref "J11") (pin "H2") (pinfunction "H2_H2") (pintype "bidirectional+no_connect"))
    )
    (net (code "172") (name "unconnected-(J11-PadH3)") (class "Default")
      (node (ref "J11") (pin "H3") (pinfunction "H3_H3") (pintype "bidirectional+no_connect"))
    )
    (net (code "173") (name "unconnected-(J11-PadH4)") (class "Default")
      (node (ref "J11") (pin "H4") (pinfunction "H4_H4") (pintype "bidirectional+no_connect"))
    )
    (net (code "174") (name "unconnected-(J11-PadH5)") (class "Default")
      (node (ref "J11") (pin "H5") (pinfunction "H5_H5") (pintype "bidirectional+no_connect"))
    )
    (net (code "175") (name "unconnected-(J11-PadH6)") (class "Default")
      (node (ref "J11") (pin "H6") (pinfunction "H6_H6") (pintype "bidirectional+no_connect"))
    )
    (net (code "176") (name "unconnected-(J11-PadH7)") (class "Default")
      (node (ref "J11") (pin "H7") (pinfunction "H7_H7") (pintype "bidirectional+no_connect"))
    )
    (net (code "177") (name "unconnected-(J11-PadH8)") (class "Default")
      (node (ref "J11") (pin "H8") (pinfunction "H8_H8") (pintype "bidirectional+no_connect"))
    )
    (net (code "178") (name "unconnected-(J11-PadI2)") (class "Default")
      (node (ref "J11") (pin "I2") (pinfunction "I2_I2") (pintype "bidirectional+no_connect"))
    )
    (net (code "179") (name "unconnected-(J11-PadI4)") (class "Default")
      (node (ref "J11") (pin "I4") (pinfunction "I4_I4") (pintype "bidirectional+no_connect"))
    )
    (net (code "180") (name "unconnected-(J11-PadI6)") (class "Default")
      (node (ref "J11") (pin "I6") (pinfunction "I6_I6") (pintype "bidirectional+no_connect"))
    )
    (net (code "181") (name "unconnected-(J11-PadI8)") (class "Default")
      (node (ref "J11") (pin "I8") (pinfunction "I8_I8") (pintype "bidirectional+no_connect"))
    )
    (net (code "182") (name "unconnected-(J11-PadJ3)") (class "Default")
      (node (ref "J11") (pin "J3") (pinfunction "J3_J3") (pintype "bidirectional+no_connect"))
    )
    (net (code "183") (name "unconnected-(J11-PadJ5)") (class "Default")
      (node (ref "J11") (pin "J5") (pinfunction "J5_J5") (pintype "bidirectional+no_connect"))
    )
    (net (code "184") (name "unconnected-(J11-PadJ7)") (class "Default")
      (node (ref "J11") (pin "J7") (pinfunction "J7_J7") (pintype "bidirectional+no_connect"))
    )
    (net (code "185") (name "unconnected-(J11-PadK2)") (class "Default")
      (node (ref "J11") (pin "K2") (pinfunction "K2_K2") (pintype "bidirectional+no_connect"))
    )
    (net (code "186") (name "unconnected-(J11-PadK3)") (class "Default")
      (node (ref "J11") (pin "K3") (pinfunction "K3_K3") (pintype "bidirectional+no_connect"))
    )
    (net (code "187") (name "unconnected-(J11-PadK4)") (class "Default")
      (node (ref "J11") (pin "K4") (pinfunction "K4_K4") (pintype "bidirectional+no_connect"))
    )
    (net (code "188") (name "unconnected-(J11-PadK5)") (class "Default")
      (node (ref "J11") (pin "K5") (pinfunction "K5_K5") (pintype "bidirectional+no_connect"))
    )
    (net (code "189") (name "unconnected-(J11-PadK6)") (class "Default")
      (node (ref "J11") (pin "K6") (pinfunction "K6_K6") (pintype "bidirectional+no_connect"))
    )
    (net (code "190") (name "unconnected-(J11-PadK7)") (class "Default")
      (node (ref "J11") (pin "K7") (pinfunction "K7_K7") (pintype "bidirectional+no_connect"))
    )
    (net (code "191") (name "unconnected-(J11-PadK8)") (class "Default")
      (node (ref "J11") (pin "K8") (pinfunction "K8_K8") (pintype "bidirectional+no_connect"))
    )
    (net (code "192") (name "unconnected-(J11-PadL2)") (class "Default")
      (node (ref "J11") (pin "L2") (pinfunction "L2_L2") (pintype "bidirectional+no_connect"))
    )
    (net (code "193") (name "unconnected-(J11-PadL4)") (class "Default")
      (node (ref "J11") (pin "L4") (pinfunction "L4_L4") (pintype "bidirectional+no_connect"))
    )
    (net (code "194") (name "unconnected-(J11-PadL6)") (class "Default")
      (node (ref "J11") (pin "L6") (pinfunction "L6_L6") (pintype "bidirectional+no_connect"))
    )
    (net (code "195") (name "unconnected-(J11-PadL8)") (class "Default")
      (node (ref "J11") (pin "L8") (pinfunction "L8_L8") (pintype "bidirectional+no_connect"))
    )
  )
)
